# ESP_LoRa_1_2.net
KiCad netlist of a schematic drawn in EAGLE
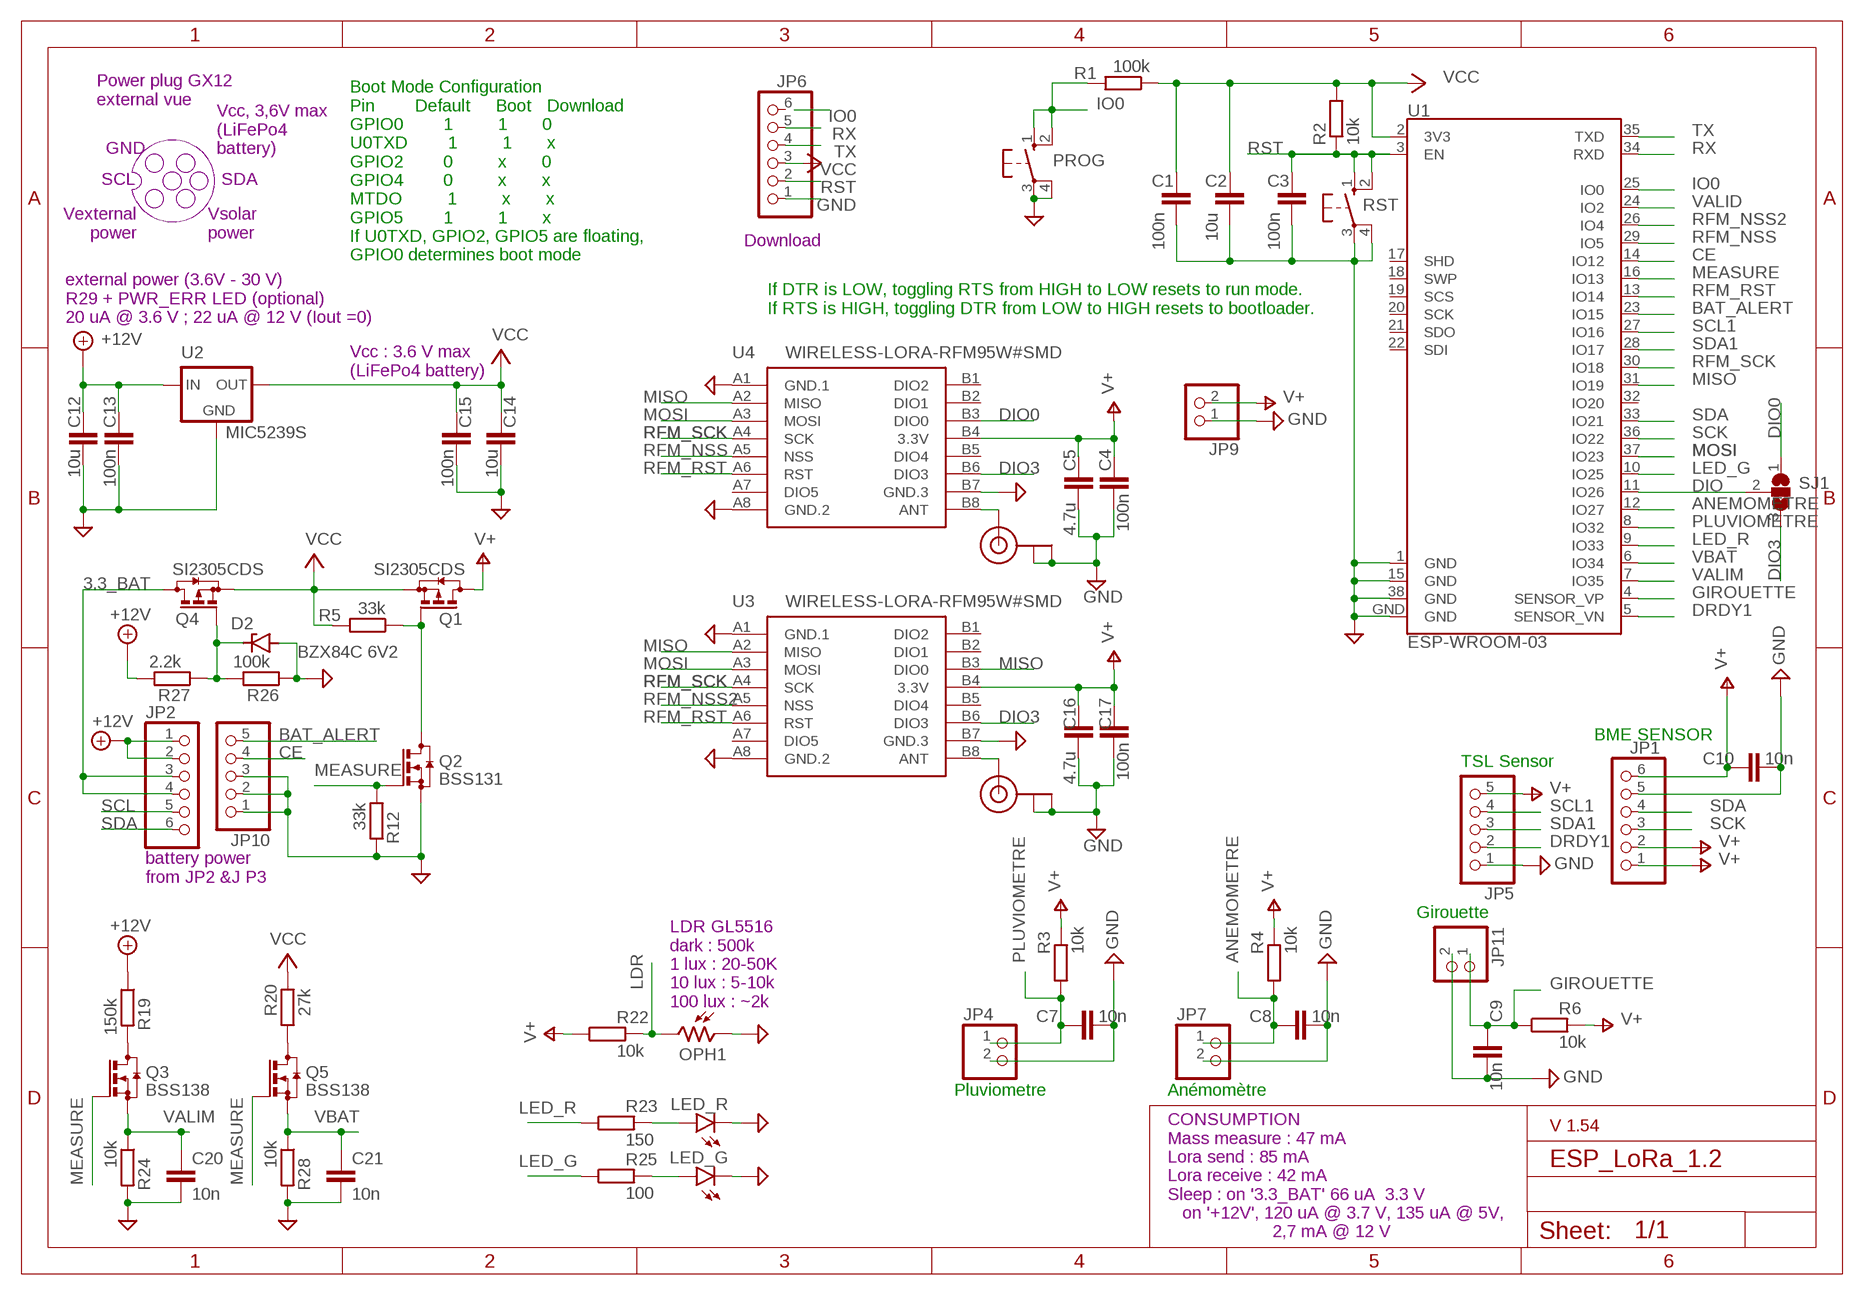
[diagram p0: schematic, sheet 1]

(export (version "E")
  (design (tool "Eeschema 10.0.6"))
  (components
    (comp (ref "C1")
      (value "100n")
      (footprint "eagle-import:C1206")
      (libsource (lib "eagle-import") (part "CC1206"))
    )
    (comp (ref "C2")
      (value "10u")
      (footprint "eagle-import:C1210")
      (libsource (lib "eagle-import") (part "CC1210"))
    )
    (comp (ref "C3")
      (value "100n")
      (footprint "eagle-import:C1206")
      (libsource (lib "eagle-import") (part "CC1206"))
    )
    (comp (ref "C4")
      (value "100n")
      (footprint "eagle-import:C1206")
      (libsource (lib "eagle-import") (part "CC1206"))
    )
    (comp (ref "C5")
      (value "4.7u")
      (footprint "eagle-import:C1210")
      (libsource (lib "eagle-import") (part "CC1210"))
    )
    (comp (ref "C7")
      (value "10n")
      (footprint "eagle-import:C1206")
      (libsource (lib "eagle-import") (part "CC1206"))
    )
    (comp (ref "C8")
      (value "10n")
      (footprint "eagle-import:C1206")
      (libsource (lib "eagle-import") (part "CC1206"))
    )
    (comp (ref "C9")
      (value "10n")
      (footprint "eagle-import:C1206")
      (libsource (lib "eagle-import") (part "CC1206"))
    )
    (comp (ref "C10")
      (value "10n")
      (footprint "eagle-import:C1206")
      (libsource (lib "eagle-import") (part "CC1206"))
    )
    (comp (ref "C12")
      (value "10u")
      (footprint "eagle-import:C1210")
      (libsource (lib "eagle-import") (part "CC1210"))
    )
    (comp (ref "C13")
      (value "100n")
      (footprint "eagle-import:C1206")
      (libsource (lib "eagle-import") (part "CC1206"))
    )
    (comp (ref "C14")
      (value "10u")
      (footprint "eagle-import:C1210")
      (libsource (lib "eagle-import") (part "CC1210"))
    )
    (comp (ref "C15")
      (value "100n")
      (footprint "eagle-import:C1206")
      (libsource (lib "eagle-import") (part "CC1206"))
    )
    (comp (ref "C16")
      (value "4.7u")
      (footprint "eagle-import:C1210")
      (libsource (lib "eagle-import") (part "CC1210"))
    )
    (comp (ref "C17")
      (value "100n")
      (footprint "eagle-import:C1206")
      (libsource (lib "eagle-import") (part "CC1206"))
    )
    (comp (ref "C20")
      (value "10n")
      (footprint "eagle-import:C1206")
      (libsource (lib "eagle-import") (part "CC1206"))
    )
    (comp (ref "C21")
      (value "10n")
      (footprint "eagle-import:C1206")
      (libsource (lib "eagle-import") (part "CC1206"))
    )
    (comp (ref "D2")
      (value "BZX84C 6V2")
      (footprint "eagle-import:TO236")
      (libsource (lib "eagle-import") (part "BZX84CSMD"))
    )
    (comp (ref "J1")
      (value "U.FL")
      (footprint "eagle-import:U.FL")
      (libsource (lib "eagle-import") (part "U.FL"))
    )
    (comp (ref "J2")
      (value "U.FL")
      (footprint "eagle-import:U.FL")
      (libsource (lib "eagle-import") (part "U.FL"))
    )
    (comp (ref "JP1")
      (value "PINHD-1X6")
      (footprint "eagle-import:1X06")
      (libsource (lib "eagle-import") (part "PINHD-1X6"))
    )
    (comp (ref "JP2")
      (value "PINHD-1X6")
      (footprint "eagle-import:1X06")
      (libsource (lib "eagle-import") (part "PINHD-1X6"))
    )
    (comp (ref "JP4")
      (value "PINHD-1X2")
      (footprint "eagle-import:1X02")
      (libsource (lib "eagle-import") (part "PINHD-1X2"))
    )
    (comp (ref "JP5")
      (value "PINHD-1X5")
      (footprint "eagle-import:1X05")
      (libsource (lib "eagle-import") (part "PINHD-1X5"))
    )
    (comp (ref "JP6")
      (value "PINHD-1X6")
      (footprint "eagle-import:1X06")
      (libsource (lib "eagle-import") (part "PINHD-1X6"))
    )
    (comp (ref "JP7")
      (value "PINHD-1X2")
      (footprint "eagle-import:1X02")
      (libsource (lib "eagle-import") (part "PINHD-1X2"))
    )
    (comp (ref "JP9")
      (value "PINHD-1X2")
      (footprint "eagle-import:1X02")
      (libsource (lib "eagle-import") (part "PINHD-1X2"))
    )
    (comp (ref "JP10")
      (value "PINHD-1X5")
      (footprint "eagle-import:1X05")
      (libsource (lib "eagle-import") (part "PINHD-1X5"))
    )
    (comp (ref "JP11")
      (value "PINHD-1X2")
      (footprint "eagle-import:1X02")
      (libsource (lib "eagle-import") (part "PINHD-1X2"))
    )
    (comp (ref "LED_G")
      (value "LEDSMT1206")
      (footprint "eagle-import:1206")
      (libsource (lib "eagle-import") (part "LEDSMT1206"))
    )
    (comp (ref "LED_R")
      (value "LEDSMT1206")
      (footprint "eagle-import:1206")
      (libsource (lib "eagle-import") (part "LEDSMT1206"))
    )
    (comp (ref "OPH1")
      (value "VT93N2")
      (footprint "eagle-import:VT900")
      (libsource (lib "eagle-import") (part "VT93N2"))
    )
    (comp (ref "PROG")
      (value "10-XX")
      (footprint "eagle-import:B3F-10XX")
      (fields (field (name "MPN") "B3F-1000"))
      (libsource (lib "eagle-import") (part "10-XX"))
    )
    (comp (ref "Q1")
      (value "SI2305CDS")
      (footprint "eagle-import:SOT23")
      (libsource (lib "eagle-import") (part "SI2305CDS"))
    )
    (comp (ref "Q2")
      (value "BSS131")
      (footprint "eagle-import:SOT23")
      (libsource (lib "eagle-import") (part "BSS131"))
    )
    (comp (ref "Q3")
      (value "BSS138")
      (footprint "eagle-import:SOT23")
      (libsource (lib "eagle-import") (part "BSS138"))
    )
    (comp (ref "Q4")
      (value "SI2305CDS")
      (footprint "eagle-import:SOT23")
      (libsource (lib "eagle-import") (part "SI2305CDS"))
    )
    (comp (ref "Q5")
      (value "BSS138")
      (footprint "eagle-import:SOT23")
      (libsource (lib "eagle-import") (part "BSS138"))
    )
    (comp (ref "R1")
      (value "100k")
      (footprint "eagle-import:R1206")
      (libsource (lib "eagle-import") (part "RR1206"))
    )
    (comp (ref "R2")
      (value "10k")
      (footprint "eagle-import:R1206")
      (libsource (lib "eagle-import") (part "RR1206"))
    )
    (comp (ref "R3")
      (value "10k")
      (footprint "eagle-import:R1206")
      (libsource (lib "eagle-import") (part "RR1206"))
    )
    (comp (ref "R4")
      (value "10k")
      (footprint "eagle-import:R1206")
      (libsource (lib "eagle-import") (part "RR1206"))
    )
    (comp (ref "R5")
      (value "33k")
      (footprint "eagle-import:R1206")
      (libsource (lib "eagle-import") (part "RR1206"))
    )
    (comp (ref "R6")
      (value "10k")
      (footprint "eagle-import:R1206")
      (libsource (lib "eagle-import") (part "RR1206"))
    )
    (comp (ref "R12")
      (value "33k")
      (footprint "eagle-import:R1206")
      (libsource (lib "eagle-import") (part "RR1206"))
    )
    (comp (ref "R19")
      (value "150k")
      (footprint "eagle-import:R1206")
      (libsource (lib "eagle-import") (part "RR1206"))
    )
    (comp (ref "R20")
      (value "27k")
      (footprint "eagle-import:R1206")
      (libsource (lib "eagle-import") (part "RR1206"))
    )
    (comp (ref "R22")
      (value "10k")
      (footprint "eagle-import:R1206")
      (libsource (lib "eagle-import") (part "RR1206"))
    )
    (comp (ref "R23")
      (value "150")
      (footprint "eagle-import:R1206")
      (libsource (lib "eagle-import") (part "RR1206"))
    )
    (comp (ref "R24")
      (value "10k")
      (footprint "eagle-import:R1206")
      (libsource (lib "eagle-import") (part "RR1206"))
    )
    (comp (ref "R25")
      (value "100")
      (footprint "eagle-import:R1206")
      (libsource (lib "eagle-import") (part "RR1206"))
    )
    (comp (ref "R26")
      (value "100k")
      (footprint "eagle-import:R1206")
      (libsource (lib "eagle-import") (part "RR1206"))
    )
    (comp (ref "R27")
      (value "2.2k")
      (footprint "eagle-import:R1206")
      (libsource (lib "eagle-import") (part "RR1206"))
    )
    (comp (ref "R28")
      (value "10k")
      (footprint "eagle-import:R1206")
      (libsource (lib "eagle-import") (part "RR1206"))
    )
    (comp (ref "RST")
      (value "10-XX")
      (footprint "eagle-import:B3F-10XX")
      (fields (field (name "MPN") "B3F-1000"))
      (libsource (lib "eagle-import") (part "10-XX"))
    )
    (comp (ref "SJ1")
      (value "SJ2W")
      (footprint "eagle-import:SJ_2")
      (libsource (lib "eagle-import") (part "SJ2W"))
    )
    (comp (ref "U1")
      (value "ESP-WROOM-03")
      (footprint "eagle-import:ESP-WROOM-03")
      (libsource (lib "eagle-import") (part "ESP-WROOM-03"))
    )
    (comp (ref "U2")
      (value "MIC5239S")
      (footprint "eagle-import:SOT223")
      (libsource (lib "eagle-import") (part "MIC5239S"))
    )
    (comp (ref "U3")
      (value "WIRELESS-LORA-RFM95W#SMD")
      (footprint "eagle-import:WIRELESS-LORA-RFM95W#SMD")
      (libsource (lib "eagle-import") (part "WIRELESS-LORA-RFM95W#SMD"))
    )
    (comp (ref "U4")
      (value "WIRELESS-LORA-RFM95W#SMD")
      (footprint "eagle-import:WIRELESS-LORA-RFM95W#SMD")
      (libsource (lib "eagle-import") (part "WIRELESS-LORA-RFM95W#SMD"))
    )
  )
  (nets
    (net (code "1") (name "+12V") (class "Default")
      (node (ref "C12") (pin "1") (pinfunction "1_1") (pintype "passive"))
      (node (ref "C13") (pin "1") (pinfunction "1_1") (pintype "passive"))
      (node (ref "JP2") (pin "1") (pinfunction "1_1") (pintype "passive"))
      (node (ref "JP2") (pin "2") (pinfunction "2_2") (pintype "passive"))
      (node (ref "R19") (pin "1") (pinfunction "1_1") (pintype "passive"))
      (node (ref "R27") (pin "2") (pinfunction "2_2") (pintype "passive"))
      (node (ref "U2") (pin "1") (pinfunction "IN_1") (pintype "input"))
    )
    (net (code "2") (name "/3.3_BAT") (class "Default")
      (node (ref "JP2") (pin "3") (pinfunction "3_3") (pintype "passive"))
      (node (ref "JP2") (pin "4") (pinfunction "4_4") (pintype "passive"))
      (node (ref "Q4") (pin "3") (pinfunction "D_3") (pintype "passive"))
    )
    (net (code "3") (name "/ANEMOMETRE") (class "Default")
      (node (ref "C8") (pin "1") (pinfunction "1_1") (pintype "passive"))
      (node (ref "JP7") (pin "1") (pinfunction "1_1") (pintype "passive"))
      (node (ref "R4") (pin "1") (pinfunction "1_1") (pintype "passive"))
      (node (ref "U1") (pin "12") (pinfunction "IO27_12") (pintype "bidirectional"))
    )
    (net (code "4") (name "/BAT_ALERT") (class "Default")
      (node (ref "JP10") (pin "5") (pinfunction "5_5") (pintype "passive"))
      (node (ref "U1") (pin "23") (pinfunction "IO15_23") (pintype "bidirectional"))
    )
    (net (code "5") (name "/CE") (class "Default")
      (node (ref "JP10") (pin "4") (pinfunction "4_4") (pintype "passive"))
      (node (ref "U1") (pin "14") (pinfunction "IO12_14") (pintype "bidirectional"))
    )
    (net (code "6") (name "/DIO") (class "Default")
      (node (ref "SJ1") (pin "2") (pinfunction "2_2") (pintype "passive"))
      (node (ref "U1") (pin "11") (pinfunction "IO26_11") (pintype "bidirectional"))
    )
    (net (code "7") (name "/DIO0") (class "Default")
      (node (ref "SJ1") (pin "1") (pinfunction "1_1") (pintype "passive"))
      (node (ref "U4") (pin "B3") (pinfunction "DIO0_B3") (pintype "bidirectional"))
    )
    (net (code "8") (name "/DIO3") (class "Default")
      (node (ref "SJ1") (pin "3") (pinfunction "3_3") (pintype "passive"))
      (node (ref "U3") (pin "B6") (pinfunction "DIO3_B6") (pintype "bidirectional"))
      (node (ref "U4") (pin "B6") (pinfunction "DIO3_B6") (pintype "bidirectional"))
    )
    (net (code "9") (name "/DRDY1") (class "Default")
      (node (ref "JP5") (pin "2") (pinfunction "2_2") (pintype "passive"))
      (node (ref "U1") (pin "5") (pinfunction "SENSOR_VN_5") (pintype "bidirectional"))
    )
    (net (code "10") (name "/GIROUETTE") (class "Default")
      (node (ref "C9") (pin "1") (pinfunction "1_1") (pintype "passive"))
      (node (ref "JP11") (pin "1") (pinfunction "1_1") (pintype "passive"))
      (node (ref "R6") (pin "1") (pinfunction "1_1") (pintype "passive"))
      (node (ref "U1") (pin "4") (pinfunction "SENSOR_VP_4") (pintype "bidirectional"))
    )
    (net (code "11") (name "/IO0") (class "Default")
      (node (ref "PROG") (pin "1") (pinfunction "S_1") (pintype "passive"))
      (node (ref "PROG") (pin "2") (pinfunction "S1_2") (pintype "passive"))
      (node (ref "R1") (pin "2") (pinfunction "2_2") (pintype "passive"))
      (node (ref "U1") (pin "25") (pinfunction "IO0_25") (pintype "bidirectional"))
    )
    (net (code "12") (name "/LDR") (class "Default")
      (node (ref "OPH1") (pin "2") (pinfunction "2_2") (pintype "passive"))
      (node (ref "R22") (pin "2") (pinfunction "2_2") (pintype "passive"))
    )
    (net (code "13") (name "/LED_G") (class "Default")
      (node (ref "R25") (pin "1") (pinfunction "1_1") (pintype "passive"))
      (node (ref "U1") (pin "10") (pinfunction "IO25_10") (pintype "bidirectional"))
    )
    (net (code "14") (name "/LED_R") (class "Default")
      (node (ref "R23") (pin "1") (pinfunction "1_1") (pintype "passive"))
      (node (ref "U1") (pin "9") (pinfunction "IO33_9") (pintype "bidirectional"))
    )
    (net (code "15") (name "/MEASURE") (class "Default")
      (node (ref "Q2") (pin "1") (pinfunction "G_1") (pintype "passive"))
      (node (ref "Q3") (pin "1") (pinfunction "G_1") (pintype "passive"))
      (node (ref "Q5") (pin "1") (pinfunction "G_1") (pintype "passive"))
      (node (ref "R12") (pin "1") (pinfunction "1_1") (pintype "passive"))
      (node (ref "U1") (pin "16") (pinfunction "IO13_16") (pintype "bidirectional"))
    )
    (net (code "16") (name "/MISO") (class "Default")
      (node (ref "U1") (pin "31") (pinfunction "IO19_31") (pintype "bidirectional"))
      (node (ref "U3") (pin "A2") (pinfunction "MISO_A2") (pintype "bidirectional"))
      (node (ref "U3") (pin "B3") (pinfunction "DIO0_B3") (pintype "bidirectional"))
      (node (ref "U4") (pin "A2") (pinfunction "MISO_A2") (pintype "bidirectional"))
    )
    (net (code "17") (name "/MOSI") (class "Default")
      (node (ref "U1") (pin "37") (pinfunction "IO23_37") (pintype "bidirectional"))
      (node (ref "U3") (pin "A3") (pinfunction "MOSI_A3") (pintype "bidirectional"))
      (node (ref "U4") (pin "A3") (pinfunction "MOSI_A3") (pintype "bidirectional"))
    )
    (net (code "18") (name "/PLUVIOMETRE") (class "Default")
      (node (ref "C7") (pin "1") (pinfunction "1_1") (pintype "passive"))
      (node (ref "JP4") (pin "1") (pinfunction "1_1") (pintype "passive"))
      (node (ref "R3") (pin "1") (pinfunction "1_1") (pintype "passive"))
      (node (ref "U1") (pin "8") (pinfunction "IO32_8") (pintype "bidirectional"))
    )
    (net (code "19") (name "/RFM_NSS") (class "Default")
      (node (ref "U1") (pin "29") (pinfunction "IO5_29") (pintype "bidirectional"))
      (node (ref "U4") (pin "A5") (pinfunction "NSS_A5") (pintype "bidirectional"))
    )
    (net (code "20") (name "/RFM_NSS2") (class "Default")
      (node (ref "U1") (pin "26") (pinfunction "IO4_26") (pintype "bidirectional"))
      (node (ref "U3") (pin "A5") (pinfunction "NSS_A5") (pintype "bidirectional"))
    )
    (net (code "21") (name "/RFM_RST") (class "Default")
      (node (ref "U1") (pin "13") (pinfunction "IO14_13") (pintype "bidirectional"))
      (node (ref "U3") (pin "A6") (pinfunction "RST_A6") (pintype "bidirectional"))
      (node (ref "U4") (pin "A6") (pinfunction "RST_A6") (pintype "bidirectional"))
    )
    (net (code "22") (name "/RFM_SCK") (class "Default")
      (node (ref "U1") (pin "30") (pinfunction "IO18_30") (pintype "bidirectional"))
      (node (ref "U3") (pin "A4") (pinfunction "SCK_A4") (pintype "bidirectional"))
      (node (ref "U4") (pin "A4") (pinfunction "SCK_A4") (pintype "bidirectional"))
    )
    (net (code "23") (name "/RST") (class "Default")
      (node (ref "C3") (pin "1") (pinfunction "1_1") (pintype "passive"))
      (node (ref "JP6") (pin "2") (pinfunction "2_2") (pintype "passive"))
      (node (ref "R2") (pin "1") (pinfunction "1_1") (pintype "passive"))
      (node (ref "RST") (pin "1") (pinfunction "S_1") (pintype "passive"))
      (node (ref "RST") (pin "2") (pinfunction "S1_2") (pintype "passive"))
      (node (ref "U1") (pin "3") (pinfunction "EN_3") (pintype "bidirectional"))
    )
    (net (code "24") (name "/RX") (class "Default")
      (node (ref "JP6") (pin "5") (pinfunction "5_5") (pintype "passive"))
      (node (ref "U1") (pin "34") (pinfunction "RXD_34") (pintype "bidirectional"))
    )
    (net (code "25") (name "/SCK") (class "Default")
      (node (ref "JP1") (pin "3") (pinfunction "3_3") (pintype "passive"))
      (node (ref "U1") (pin "36") (pinfunction "IO22_36") (pintype "bidirectional"))
    )
    (net (code "26") (name "/SCL") (class "Default")
      (node (ref "JP2") (pin "5") (pinfunction "5_5") (pintype "passive"))
    )
    (net (code "27") (name "/SCL1") (class "Default")
      (node (ref "JP5") (pin "4") (pinfunction "4_4") (pintype "passive"))
      (node (ref "U1") (pin "27") (pinfunction "IO16_27") (pintype "bidirectional"))
    )
    (net (code "28") (name "/SDA") (class "Default")
      (node (ref "JP1") (pin "4") (pinfunction "4_4") (pintype "passive"))
      (node (ref "JP2") (pin "6") (pinfunction "6_6") (pintype "passive"))
      (node (ref "U1") (pin "33") (pinfunction "IO21_33") (pintype "bidirectional"))
    )
    (net (code "29") (name "/SDA1") (class "Default")
      (node (ref "JP5") (pin "3") (pinfunction "3_3") (pintype "passive"))
      (node (ref "U1") (pin "28") (pinfunction "IO17_28") (pintype "bidirectional"))
    )
    (net (code "30") (name "/TX") (class "Default")
      (node (ref "JP6") (pin "4") (pinfunction "4_4") (pintype "passive"))
      (node (ref "U1") (pin "35") (pinfunction "TXD_35") (pintype "bidirectional"))
    )
    (net (code "31") (name "/VALID") (class "Default")
      (node (ref "U1") (pin "24") (pinfunction "IO2_24") (pintype "bidirectional"))
    )
    (net (code "32") (name "/VALIM") (class "Default")
      (node (ref "C20") (pin "1") (pinfunction "1_1") (pintype "passive"))
      (node (ref "Q3") (pin "2") (pinfunction "S_2") (pintype "passive"))
      (node (ref "R24") (pin "1") (pinfunction "1_1") (pintype "passive"))
      (node (ref "U1") (pin "7") (pinfunction "IO35_7") (pintype "bidirectional"))
    )
    (net (code "33") (name "/VBAT") (class "Default")
      (node (ref "C21") (pin "1") (pinfunction "1_1") (pintype "passive"))
      (node (ref "Q5") (pin "2") (pinfunction "S_2") (pintype "passive"))
      (node (ref "R28") (pin "1") (pinfunction "1_1") (pintype "passive"))
      (node (ref "U1") (pin "6") (pinfunction "IO34_6") (pintype "bidirectional"))
    )
    (net (code "34") (name "GND") (class "Default")
      (node (ref "C1") (pin "2") (pinfunction "2_2") (pintype "passive"))
      (node (ref "C10") (pin "2") (pinfunction "2_2") (pintype "passive"))
      (node (ref "C12") (pin "2") (pinfunction "2_2") (pintype "passive"))
      (node (ref "C13") (pin "2") (pinfunction "2_2") (pintype "passive"))
      (node (ref "C14") (pin "2") (pinfunction "2_2") (pintype "passive"))
      (node (ref "C15") (pin "2") (pinfunction "2_2") (pintype "passive"))
      (node (ref "C16") (pin "2") (pinfunction "2_2") (pintype "passive"))
      (node (ref "C17") (pin "2") (pinfunction "2_2") (pintype "passive"))
      (node (ref "C2") (pin "2") (pinfunction "2_2") (pintype "passive"))
      (node (ref "C20") (pin "2") (pinfunction "2_2") (pintype "passive"))
      (node (ref "C21") (pin "2") (pinfunction "2_2") (pintype "passive"))
      (node (ref "C3") (pin "2") (pinfunction "2_2") (pintype "passive"))
      (node (ref "C4") (pin "2") (pinfunction "2_2") (pintype "passive"))
      (node (ref "C5") (pin "2") (pinfunction "2_2") (pintype "passive"))
      (node (ref "C7") (pin "2") (pinfunction "2_2") (pintype "passive"))
      (node (ref "C8") (pin "2") (pinfunction "2_2") (pintype "passive"))
      (node (ref "C9") (pin "2") (pinfunction "2_2") (pintype "passive"))
      (node (ref "D2") (pin "A") (pinfunction "A_A") (pintype "passive"))
      (node (ref "J1") (pin "1") (pinfunction "GND_1") (pintype "passive"))
      (node (ref "J1") (pin "2") (pinfunction "GND_2") (pintype "passive"))
      (node (ref "J2") (pin "1") (pinfunction "GND_1") (pintype "passive"))
      (node (ref "J2") (pin "2") (pinfunction "GND_2") (pintype "passive"))
      (node (ref "JP1") (pin "5") (pinfunction "5_5") (pintype "passive"))
      (node (ref "JP10") (pin "1") (pinfunction "1_1") (pintype "passive"))
      (node (ref "JP10") (pin "2") (pinfunction "2_2") (pintype "passive"))
      (node (ref "JP10") (pin "3") (pinfunction "3_3") (pintype "passive"))
      (node (ref "JP11") (pin "2") (pinfunction "2_2") (pintype "passive"))
      (node (ref "JP4") (pin "2") (pinfunction "2_2") (pintype "passive"))
      (node (ref "JP5") (pin "1") (pinfunction "1_1") (pintype "passive"))
      (node (ref "JP6") (pin "1") (pinfunction "1_1") (pintype "passive"))
      (node (ref "JP7") (pin "2") (pinfunction "2_2") (pintype "passive"))
      (node (ref "JP9") (pin "1") (pinfunction "1_1") (pintype "passive"))
      (node (ref "LED_G") (pin "C") (pinfunction "C_C") (pintype "passive"))
      (node (ref "LED_R") (pin "C") (pinfunction "C_C") (pintype "passive"))
      (node (ref "OPH1") (pin "1") (pinfunction "1_1") (pintype "passive"))
      (node (ref "PROG") (pin "3") (pinfunction "P_3") (pintype "passive"))
      (node (ref "PROG") (pin "4") (pinfunction "P1_4") (pintype "passive"))
      (node (ref "Q2") (pin "2") (pinfunction "S_2") (pintype "passive"))
      (node (ref "R12") (pin "2") (pinfunction "2_2") (pintype "passive"))
      (node (ref "R24") (pin "2") (pinfunction "2_2") (pintype "passive"))
      (node (ref "R26") (pin "1") (pinfunction "1_1") (pintype "passive"))
      (node (ref "R28") (pin "2") (pinfunction "2_2") (pintype "passive"))
      (node (ref "RST") (pin "3") (pinfunction "P_3") (pintype "passive"))
      (node (ref "RST") (pin "4") (pinfunction "P1_4") (pintype "passive"))
      (node (ref "U1") (pin "1") (pinfunction "GND_1") (pintype "bidirectional"))
      (node (ref "U1") (pin "15") (pinfunction "GND_15") (pintype "bidirectional"))
      (node (ref "U1") (pin "38") (pinfunction "GND_38") (pintype "bidirectional"))
      (node (ref "U1") (pin "GND") (pinfunction "GND_GND") (pintype "bidirectional"))
      (node (ref "U2") (pin "2") (pinfunction "GND_2") (pintype "passive"))
      (node (ref "U2") (pin "4") (pinfunction "GND_4") (pintype "passive"))
      (node (ref "U3") (pin "A1") (pinfunction "GND.1_A1") (pintype "power_in"))
      (node (ref "U3") (pin "A8") (pinfunction "GND.2_A8") (pintype "power_in"))
      (node (ref "U3") (pin "B7") (pinfunction "GND.3_B7") (pintype "power_in"))
      (node (ref "U4") (pin "A1") (pinfunction "GND.1_A1") (pintype "power_in"))
      (node (ref "U4") (pin "A8") (pinfunction "GND.2_A8") (pintype "power_in"))
      (node (ref "U4") (pin "B7") (pinfunction "GND.3_B7") (pintype "power_in"))
    )
    (net (code "35") (name "Net-(J1-SIGNAL)") (class "Default")
      (node (ref "J1") (pin "3") (pinfunction "SIGNAL_3") (pintype "passive"))
      (node (ref "U3") (pin "B8") (pinfunction "ANT_B8") (pintype "passive"))
    )
    (net (code "36") (name "Net-(J2-SIGNAL)") (class "Default")
      (node (ref "J2") (pin "3") (pinfunction "SIGNAL_3") (pintype "passive"))
      (node (ref "U4") (pin "B8") (pinfunction "ANT_B8") (pintype "passive"))
    )
    (net (code "37") (name "Net-(LED_G-PadA)") (class "Default")
      (node (ref "LED_G") (pin "A") (pinfunction "A_A") (pintype "passive"))
      (node (ref "R25") (pin "2") (pinfunction "2_2") (pintype "passive"))
    )
    (net (code "38") (name "Net-(LED_R-PadA)") (class "Default")
      (node (ref "LED_R") (pin "A") (pinfunction "A_A") (pintype "passive"))
      (node (ref "R23") (pin "2") (pinfunction "2_2") (pintype "passive"))
    )
    (net (code "39") (name "Net-(Q1-G)") (class "Default")
      (node (ref "Q1") (pin "1") (pinfunction "G_1") (pintype "passive"))
      (node (ref "Q2") (pin "3") (pinfunction "D_3") (pintype "passive"))
      (node (ref "R5") (pin "1") (pinfunction "1_1") (pintype "passive"))
    )
    (net (code "40") (name "Net-(Q3-D)") (class "Default")
      (node (ref "Q3") (pin "3") (pinfunction "D_3") (pintype "passive"))
      (node (ref "R19") (pin "2") (pinfunction "2_2") (pintype "passive"))
    )
    (net (code "41") (name "Net-(Q4-G)") (class "Default")
      (node (ref "D2") (pin "C") (pinfunction "C_C") (pintype "passive"))
      (node (ref "Q4") (pin "1") (pinfunction "G_1") (pintype "passive"))
      (node (ref "R26") (pin "2") (pinfunction "2_2") (pintype "passive"))
      (node (ref "R27") (pin "1") (pinfunction "1_1") (pintype "passive"))
    )
    (net (code "42") (name "Net-(Q5-D)") (class "Default")
      (node (ref "Q5") (pin "3") (pinfunction "D_3") (pintype "passive"))
      (node (ref "R20") (pin "1") (pinfunction "1_1") (pintype "passive"))
    )
    (net (code "43") (name "V+") (class "Default")
      (node (ref "C10") (pin "1") (pinfunction "1_1") (pintype "passive"))
      (node (ref "C16") (pin "1") (pinfunction "1_1") (pintype "passive"))
      (node (ref "C17") (pin "1") (pinfunction "1_1") (pintype "passive"))
      (node (ref "C4") (pin "1") (pinfunction "1_1") (pintype "passive"))
      (node (ref "C5") (pin "1") (pinfunction "1_1") (pintype "passive"))
      (node (ref "JP1") (pin "1") (pinfunction "1_1") (pintype "passive"))
      (node (ref "JP1") (pin "2") (pinfunction "2_2") (pintype "passive"))
      (node (ref "JP1") (pin "6") (pinfunction "6_6") (pintype "passive"))
      (node (ref "JP5") (pin "5") (pinfunction "5_5") (pintype "passive"))
      (node (ref "JP9") (pin "2") (pinfunction "2_2") (pintype "passive"))
      (node (ref "Q1") (pin "3") (pinfunction "D_3") (pintype "passive"))
      (node (ref "R22") (pin "1") (pinfunction "1_1") (pintype "passive"))
      (node (ref "R3") (pin "2") (pinfunction "2_2") (pintype "passive"))
      (node (ref "R4") (pin "2") (pinfunction "2_2") (pintype "passive"))
      (node (ref "R6") (pin "2") (pinfunction "2_2") (pintype "passive"))
      (node (ref "U3") (pin "B4") (pinfunction "3.3V_B4") (pintype "power_in"))
      (node (ref "U4") (pin "B4") (pinfunction "3.3V_B4") (pintype "power_in"))
    )
    (net (code "44") (name "VCC") (class "Default")
      (node (ref "C1") (pin "1") (pinfunction "1_1") (pintype "passive"))
      (node (ref "C14") (pin "1") (pinfunction "1_1") (pintype "passive"))
      (node (ref "C15") (pin "1") (pinfunction "1_1") (pintype "passive"))
      (node (ref "C2") (pin "1") (pinfunction "1_1") (pintype "passive"))
      (node (ref "JP6") (pin "3") (pinfunction "3_3") (pintype "passive"))
      (node (ref "Q1") (pin "2") (pinfunction "S_2") (pintype "passive"))
      (node (ref "Q4") (pin "2") (pinfunction "S_2") (pintype "passive"))
      (node (ref "R1") (pin "1") (pinfunction "1_1") (pintype "passive"))
      (node (ref "R2") (pin "2") (pinfunction "2_2") (pintype "passive"))
      (node (ref "R20") (pin "2") (pinfunction "2_2") (pintype "passive"))
      (node (ref "R5") (pin "2") (pinfunction "2_2") (pintype "passive"))
      (node (ref "U1") (pin "2") (pinfunction "3V3_2") (pintype "bidirectional"))
      (node (ref "U2") (pin "3") (pinfunction "OUT_3") (pintype "passive"))
    )
    (net (code "45") (name "unconnected-(JP6-Pad6)") (class "Default")
      (node (ref "JP6") (pin "6") (pinfunction "6_6") (pintype "passive"))
    )
    (net (code "46") (name "unconnected-(U1-IO20-Pad32)") (class "Default")
      (node (ref "U1") (pin "32") (pinfunction "IO20_32") (pintype "bidirectional"))
    )
    (net (code "47") (name "unconnected-(U1-SCK-Pad20)") (class "Default")
      (node (ref "U1") (pin "20") (pinfunction "SCK_20") (pintype "bidirectional"))
    )
    (net (code "48") (name "unconnected-(U1-SCS-Pad19)") (class "Default")
      (node (ref "U1") (pin "19") (pinfunction "SCS_19") (pintype "bidirectional"))
    )
    (net (code "49") (name "unconnected-(U1-SDI-Pad22)") (class "Default")
      (node (ref "U1") (pin "22") (pinfunction "SDI_22") (pintype "bidirectional"))
    )
    (net (code "50") (name "unconnected-(U1-SDO-Pad21)") (class "Default")
      (node (ref "U1") (pin "21") (pinfunction "SDO_21") (pintype "bidirectional"))
    )
    (net (code "51") (name "unconnected-(U1-SHD-Pad17)") (class "Default")
      (node (ref "U1") (pin "17") (pinfunction "SHD_17") (pintype "bidirectional"))
    )
    (net (code "52") (name "unconnected-(U1-SWP-Pad18)") (class "Default")
      (node (ref "U1") (pin "18") (pinfunction "SWP_18") (pintype "bidirectional"))
    )
    (net (code "53") (name "unconnected-(U3-DIO1-PadB2)") (class "Default")
      (node (ref "U3") (pin "B2") (pinfunction "DIO1_B2") (pintype "bidirectional"))
    )
    (net (code "54") (name "unconnected-(U3-DIO2-PadB1)") (class "Default")
      (node (ref "U3") (pin "B1") (pinfunction "DIO2_B1") (pintype "bidirectional"))
    )
    (net (code "55") (name "unconnected-(U3-DIO4-PadB5)") (class "Default")
      (node (ref "U3") (pin "B5") (pinfunction "DIO4_B5") (pintype "bidirectional"))
    )
    (net (code "56") (name "unconnected-(U3-DIO5-PadA7)") (class "Default")
      (node (ref "U3") (pin "A7") (pinfunction "DIO5_A7") (pintype "bidirectional"))
    )
    (net (code "57") (name "unconnected-(U4-DIO1-PadB2)") (class "Default")
      (node (ref "U4") (pin "B2") (pinfunction "DIO1_B2") (pintype "bidirectional"))
    )
    (net (code "58") (name "unconnected-(U4-DIO2-PadB1)") (class "Default")
      (node (ref "U4") (pin "B1") (pinfunction "DIO2_B1") (pintype "bidirectional"))
    )
    (net (code "59") (name "unconnected-(U4-DIO4-PadB5)") (class "Default")
      (node (ref "U4") (pin "B5") (pinfunction "DIO4_B5") (pintype "bidirectional"))
    )
    (net (code "60") (name "unconnected-(U4-DIO5-PadA7)") (class "Default")
      (node (ref "U4") (pin "A7") (pinfunction "DIO5_A7") (pintype "bidirectional"))
    )
  )
)
